# thermocouple.net
KiCad netlist of a schematic drawn in Altium Designer
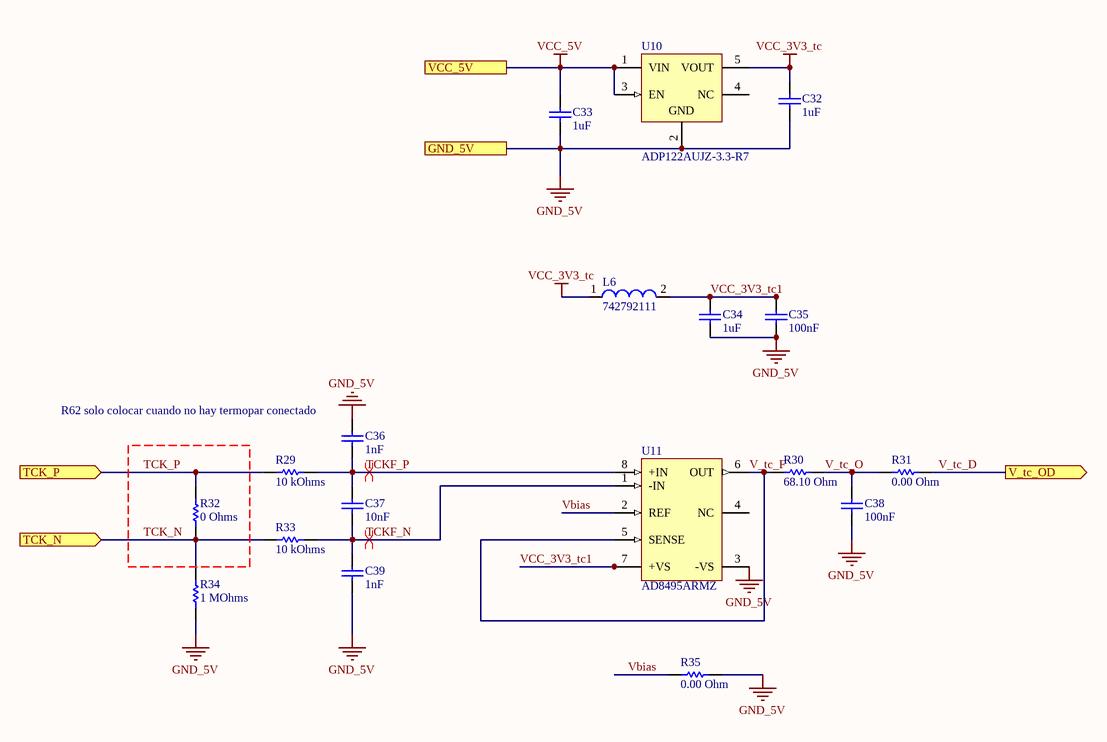
[diagram p0: thermocouple.SchDoc]

(export (version "E")
  (design (tool "Eeschema 10.0.6"))
  (components
    (comp (ref "C32")
      (value "1uF")
      (footprint "CAPC0603(1608)100_N")
      (description "CAP 1uF 50V ±20% 0603 (1608 Metric) Thickness 1mm SMD")
      (fields (field (name "TOLERANCE") "Â±20%") (field (name "Comment") "CAP 1uF 50V 0603(1608)"))
      (libsource (lib "Altium Content Vault") (part "CAP"))
    )
    (comp (ref "C33")
      (value "1uF")
      (footprint "CAPC0603(1608)100_N")
      (description "CAP 1uF 50V ±20% 0603 (1608 Metric) Thickness 1mm SMD")
      (fields (field (name "TOLERANCE") "Â±20%") (field (name "Comment") "CAP 1uF 50V 0603(1608)"))
      (libsource (lib "Altium Content Vault") (part "CAP"))
    )
    (comp (ref "C34")
      (value "1uF")
      (footprint "CAPC0603(1608)100_L")
      (description "CAP 1uF 50V ±20% 0603 (1608 Metric) Thickness 1mm SMD")
      (fields (field (name "TOLERANCE") "Â±20%") (field (name "Comment") "CAP 1uF 50V 0603(1608)"))
      (libsource (lib "Altium Content Vault") (part "CAP"))
    )
    (comp (ref "C35")
      (value "100nF")
      (footprint "CAPC0603(1608)100_L")
      (description "CAP 100nF 50V ±5% 0603 (1608 Metric) Thickness 1mm SMD")
      (fields (field (name "TOLERANCE") "Â±5%") (field (name "Comment") "CAP 100nF 50V 0603(1608)"))
      (libsource (lib "Altium Content Vault") (part "CAP"))
    )
    (comp (ref "C36")
      (value "1nF")
      (footprint "CAPC0603(1608)100_L")
      (description "CAP 1nF 25V ±5% 0603 (1608 Metric) Thickness 1mm SMD")
      (fields (field (name "TOLERANCE") "Â±5%") (field (name "Comment") "CAP 1nF 25V 0603(1608)"))
      (libsource (lib "Altium Content Vault") (part "CAP"))
    )
    (comp (ref "C37")
      (value "10nF")
      (footprint "CAPC0603(1608)100_L")
      (description "CAP 10nF 25V ±5% 0603 (1608 Metric) Thickness 1mm SMD")
      (fields (field (name "TOLERANCE") "Â±5%") (field (name "Comment") "CAP 10nF 25V 0603(1608)"))
      (libsource (lib "Altium Content Vault") (part "CAP"))
    )
    (comp (ref "C38")
      (value "100nF")
      (footprint "CAPC0603(1608)100_N")
      (description "CAP 100nF 10V ±10% 0603 (1608 Metric) Thickness 1mm SMD")
      (fields (field (name "TOLERANCE") "Â±10%") (field (name "Comment") "CAP 100nF 10V 0603(1608)"))
      (libsource (lib "Altium Content Vault") (part "CAP"))
    )
    (comp (ref "C39")
      (value "1nF")
      (footprint "CAPC0603(1608)100_L")
      (description "CAP 1nF 25V ±5% 0603 (1608 Metric) Thickness 1mm SMD")
      (fields (field (name "TOLERANCE") "Â±5%") (field (name "Comment") "CAP 1nF 25V 0603(1608)"))
      (libsource (lib "Altium Content Vault") (part "CAP"))
    )
    (comp (ref "L6")
      (value "742792111")
      (footprint "SMD-1206")
      (description "SMD EMI Suppression Ferrite Bead WE-CBF, Z = 26 Ohm")
      (libsource (lib "Altium Content Vault") (part "PAS-IND-INDUCTOR-2"))
    )
    (comp (ref "R29")
      (value "10 kOhms")
      (footprint "RESC3116X65X50NL20T20")
      (fields (field (name "PART NUMBER") "CRCW120610K0FKEAHP") (field (name "MANUFACTURER") "Vishay Dale"))
      (libsource (lib "Altium Content Vault") (part "RES"))
    )
    (comp (ref "R30")
      (value "68.10 Ohm")
      (footprint "RESC0805(2012)_N")
      (description "68R1 0.125W 1% 0805 (2012 Metric)  SMD")
      (fields (field (name "POWER") "0.125 W") (field (name "TOLERANCE") "1 %"))
      (libsource (lib "Altium Content Vault") (part "RES"))
    )
    (comp (ref "R31")
      (value "0.00 Ohm")
      (footprint "RESC0603(1608)_N")
      (description "Jumper 0603 (1608 Metric)")
      (fields (field (name "POWER") "None") (field (name "Comment") "Jumper 0603(1608)"))
      (libsource (lib "Altium Content Vault") (part "RES"))
    )
    (comp (ref "R32")
      (value "0 Ohms")
      (footprint "RESC3216X60X45LL10T20")
      (fields (field (name "PART NUMBER") "CRCW12060000Z0EB") (field (name "MANUFACTURER") "Vishay Dale"))
      (libsource (lib "Altium Content Vault") (part "RES"))
    )
    (comp (ref "R33")
      (value "10 kOhms")
      (footprint "RESC3116X65X50NL20T20")
      (fields (field (name "PART NUMBER") "CRCW120610K0FKEAHP") (field (name "MANUFACTURER") "Vishay Dale"))
      (libsource (lib "Altium Content Vault") (part "RES"))
    )
    (comp (ref "R34")
      (value "1 MOhms")
      (footprint "RESC3216X70X50LL05T20")
      (fields (field (name "MANUFACTURER") "Panasonic") (field (name "PART NUMBER") "ERJ-8GEYJ105V"))
      (libsource (lib "Altium Content Vault") (part "RES"))
    )
    (comp (ref "R35")
      (value "0.00 Ohm")
      (footprint "RESC0603(1608)_L")
      (description "Jumper 0603 (1608 Metric)")
      (fields (field (name "POWER") "None") (field (name "Comment") "Jumper 0603(1608)"))
      (libsource (lib "Altium Content Vault") (part "RES"))
    )
    (comp (ref "U10")
      (value "ADP122AUJZ-3.3-R7")
      (footprint "ADI-UJ-5_L")
      (fields (field (name "MANUFACTURER") "Analog Devices"))
      (libsource (lib "Altium Content Vault") (part "ADI-ADP1XX-UJ-5"))
    )
    (comp (ref "U11")
      (value "AD8495ARMZ")
      (footprint "DGK0008A_L")
      (fields (field (name "MANUFACTURER") "Analog Devices"))
      (libsource (lib "Altium_Library_POWERLAB") (part "AD8495ARMZ"))
    )
  )
  (nets
    (net (code "1") (name "/TCKF_N") (class "Default")
      (node (ref "C37") (pin "2") (pinfunction "2_2") (pintype "passive"))
      (node (ref "C39") (pin "1") (pinfunction "1_1") (pintype "passive"))
      (node (ref "R33") (pin "1") (pinfunction "1_1") (pintype "passive"))
      (node (ref "U11") (pin "1") (pinfunction "-IN_1") (pintype "input"))
    )
    (net (code "2") (name "/TCKF_P") (class "Default")
      (node (ref "C36") (pin "2") (pinfunction "2_2") (pintype "passive"))
      (node (ref "C37") (pin "1") (pinfunction "1_1") (pintype "passive"))
      (node (ref "R29") (pin "1") (pinfunction "1_1") (pintype "passive"))
      (node (ref "U11") (pin "8") (pinfunction "+IN_8") (pintype "input"))
    )
    (net (code "3") (name "/TCK_N") (class "Default")
      (node (ref "R32") (pin "1") (pinfunction "1_1") (pintype "passive"))
      (node (ref "R33") (pin "2") (pinfunction "2_2") (pintype "passive"))
      (node (ref "R34") (pin "2") (pinfunction "2_2") (pintype "passive"))
    )
    (net (code "4") (name "/TCK_P") (class "Default")
      (node (ref "R29") (pin "2") (pinfunction "2_2") (pintype "passive"))
      (node (ref "R32") (pin "2") (pinfunction "2_2") (pintype "passive"))
    )
    (net (code "5") (name "/VCC_3V3_tc1") (class "Default")
      (node (ref "C34") (pin "2") (pinfunction "2_2") (pintype "passive"))
      (node (ref "C35") (pin "2") (pinfunction "2_2") (pintype "passive"))
      (node (ref "L6") (pin "2") (pinfunction "2_2") (pintype "passive"))
      (node (ref "U11") (pin "7") (pinfunction "+VS_7") (pintype "power_in"))
    )
    (net (code "6") (name "/V_tc_D") (class "Default")
      (node (ref "R31") (pin "1") (pinfunction "1_1") (pintype "passive"))
    )
    (net (code "7") (name "/V_tc_F") (class "Default")
      (node (ref "R30") (pin "2") (pinfunction "2_2") (pintype "passive"))
      (node (ref "U11") (pin "5") (pinfunction "SENSE_5") (pintype "input"))
      (node (ref "U11") (pin "6") (pinfunction "OUT_6") (pintype "output"))
    )
    (net (code "8") (name "/V_tc_O") (class "Default")
      (node (ref "C38") (pin "2") (pinfunction "2_2") (pintype "passive"))
      (node (ref "R30") (pin "1") (pinfunction "1_1") (pintype "passive"))
      (node (ref "R31") (pin "2") (pinfunction "2_2") (pintype "passive"))
    )
    (net (code "9") (name "/Vbias") (class "Default")
      (node (ref "R35") (pin "1") (pinfunction "1_1") (pintype "passive"))
      (node (ref "U11") (pin "2") (pinfunction "REF_2") (pintype "input"))
    )
    (net (code "10") (name "GND_5V") (class "Default")
      (node (ref "C32") (pin "1") (pinfunction "1_1") (pintype "passive"))
      (node (ref "C33") (pin "1") (pinfunction "1_1") (pintype "passive"))
      (node (ref "C34") (pin "1") (pinfunction "1_1") (pintype "passive"))
      (node (ref "C35") (pin "1") (pinfunction "1_1") (pintype "passive"))
      (node (ref "C36") (pin "1") (pinfunction "1_1") (pintype "passive"))
      (node (ref "C38") (pin "1") (pinfunction "1_1") (pintype "passive"))
      (node (ref "C39") (pin "2") (pinfunction "2_2") (pintype "passive"))
      (node (ref "R34") (pin "1") (pinfunction "1_1") (pintype "passive"))
      (node (ref "R35") (pin "2") (pinfunction "2_2") (pintype "passive"))
      (node (ref "U10") (pin "2") (pinfunction "GND_2") (pintype "power_in"))
      (node (ref "U11") (pin "3") (pinfunction "-VS_3") (pintype "power_in"))
    )
    (net (code "11") (name "VCC_3V3_tc") (class "Default")
      (node (ref "C32") (pin "2") (pinfunction "2_2") (pintype "passive"))
      (node (ref "L6") (pin "1") (pinfunction "1_1") (pintype "passive"))
      (node (ref "U10") (pin "5") (pinfunction "VOUT_5") (pintype "power_in"))
    )
    (net (code "12") (name "VCC_5V") (class "Default")
      (node (ref "C33") (pin "2") (pinfunction "2_2") (pintype "passive"))
      (node (ref "U10") (pin "1") (pinfunction "VIN_1") (pintype "power_in"))
      (node (ref "U10") (pin "3") (pinfunction "EN_3") (pintype "input"))
    )
    (net (code "13") (name "unconnected-(U10-NC-Pad4)") (class "Default")
      (node (ref "U10") (pin "4") (pinfunction "NC_4") (pintype "passive"))
    )
    (net (code "14") (name "unconnected-(U11-NC-Pad4)") (class "Default")
      (node (ref "U11") (pin "4") (pinfunction "NC_4") (pintype "passive"))
    )
  )
)
